# Interface_Accelerometer_1.net
KiCad netlist of a schematic drawn in Altium Designer
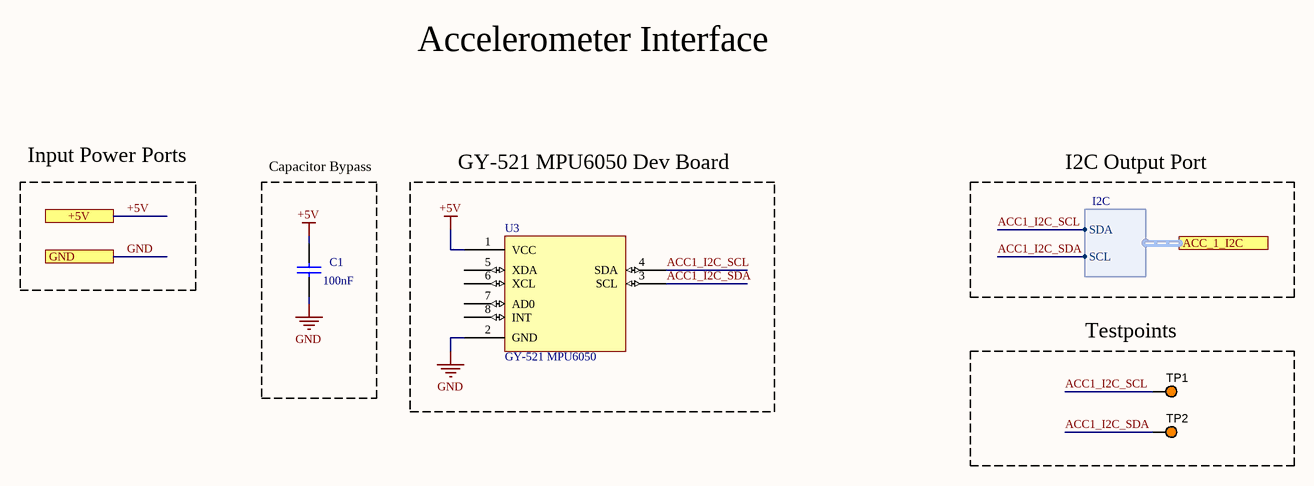
[diagram p0: Interface_Accelerometer_1.SchDoc]

(export (version "E")
  (design (tool "Eeschema 10.0.6"))
  (components
    (comp (ref "C1") (value "100nF") (footprint "CAP200") (libsource (lib "LIBEBAL") (part "CAP")))
    (comp (ref "TP1")
      (value "5003")
      (footprint "KSTN-5003")
      (description "Test Point, Orange, Height 4.6 mm, Tail Length 3 mm, 1-Pin THD, RoHS")
      (fields (field (name "MANUFACTURER") "Keystone"))
      (libsource (lib "TD") (part "TESTPOINT_ORANGE"))
    )
    (comp (ref "TP2")
      (value "5003")
      (footprint "KSTN-5003")
      (description "Test Point, Orange, Height 4.6 mm, Tail Length 3 mm, 1-Pin THD, RoHS")
      (fields (field (name "MANUFACTURER") "Keystone"))
      (libsource (lib "TD") (part "TESTPOINT_ORANGE"))
    )
    (comp (ref "U3")
      (value "GY-521 MPU6050")
      (footprint "GY-521 MPU6050")
      (libsource (lib "SiProFaSi") (part "GY-521 MPU6050"))
    )
  )
  (nets
    (net (code "2") (name "+5V") (class "Default")
      (node (ref "C1") (pin "1") (pinfunction "1_1") (pintype "passive"))
      (node (ref "U3") (pin "1") (pinfunction "VCC_1") (pintype "power_in"))
    )
    (net (code "3") (name "/ACC1_I2C_SCL") (class "Default")
      (node (ref "TP1") (pin "1") (pinfunction "1_1") (pintype "passive"))
      (node (ref "U3") (pin "4") (pinfunction "SDA_4") (pintype "bidirectional"))
    )
    (net (code "4") (name "/ACC1_I2C_SDA") (class "Default")
      (node (ref "TP2") (pin "1") (pinfunction "1_1") (pintype "passive"))
      (node (ref "U3") (pin "3") (pinfunction "SCL_3") (pintype "bidirectional"))
    )
    (net (code "6") (name "GND") (class "Default")
      (node (ref "C1") (pin "2") (pinfunction "2_2") (pintype "passive"))
      (node (ref "U3") (pin "2") (pinfunction "GND_2") (pintype "passive"))
    )
    (net (code "7") (name "unconnected-(U3-AD0-Pad7)") (class "Default")
      (node (ref "U3") (pin "7") (pinfunction "AD0_7") (pintype "bidirectional"))
    )
    (net (code "8") (name "unconnected-(U3-INT-Pad8)") (class "Default")
      (node (ref "U3") (pin "8") (pinfunction "INT_8") (pintype "bidirectional"))
    )
    (net (code "9") (name "unconnected-(U3-XCL-Pad6)") (class "Default")
      (node (ref "U3") (pin "6") (pinfunction "XCL_6") (pintype "bidirectional"))
    )
    (net (code "10") (name "unconnected-(U3-XDA-Pad5)") (class "Default")
      (node (ref "U3") (pin "5") (pinfunction "XDA_5") (pintype "bidirectional"))
    )
  )
)
